# PIC32MZ.net
KiCad netlist of a schematic drawn in Altium Designer
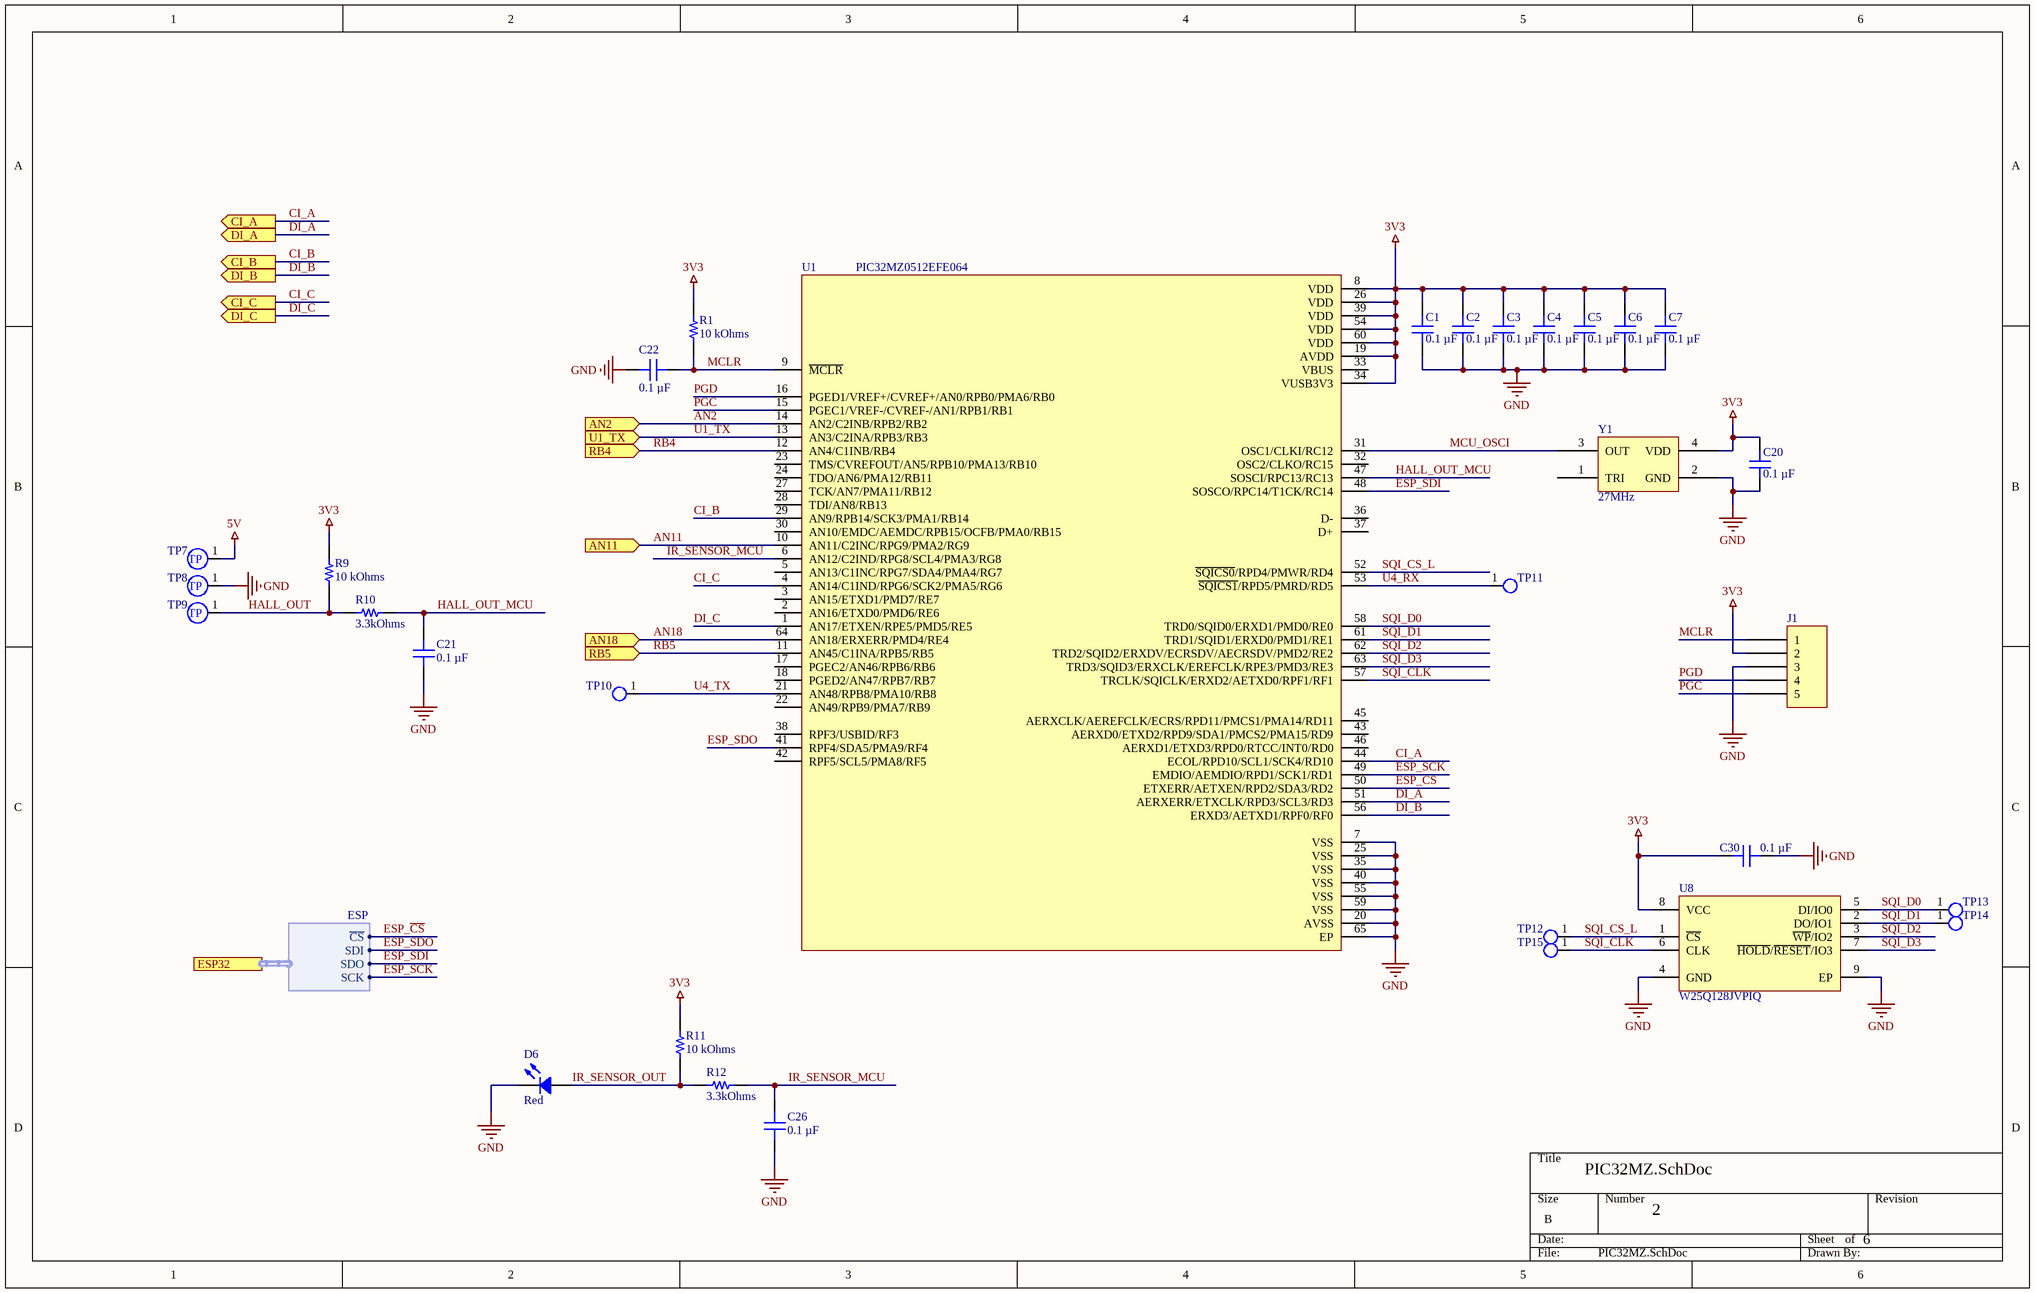
[diagram p0: PIC32MZ.SchDoc]

(export (version "E")
  (design (tool "Eeschema 10.0.6"))
  (components
    (comp (ref "C1")
      (value "0.1 µF")
      (footprint "CAP 0402_1005")
      (description "CAP CER 0.1UF 25V X5R 0402")
      (fields
        (field (name "PART NUMBER") "C1005X5R1E104K050BC")
        (field (name "MANUFACTURER") "TDK Corporation")
      )
      (libsource (lib "Celestial Altium Library - altium_library") (part "Capacitor"))
    )
    (comp (ref "C2")
      (value "0.1 µF")
      (footprint "CAP 0402_1005")
      (description "CAP CER 0.1UF 25V X5R 0402")
      (fields
        (field (name "PART NUMBER") "C1005X5R1E104K050BC")
        (field (name "MANUFACTURER") "TDK Corporation")
      )
      (libsource (lib "Celestial Altium Library - altium_library") (part "Capacitor"))
    )
    (comp (ref "C3")
      (value "0.1 µF")
      (footprint "CAP 0402_1005")
      (description "CAP CER 0.1UF 25V X5R 0402")
      (fields
        (field (name "PART NUMBER") "C1005X5R1E104K050BC")
        (field (name "MANUFACTURER") "TDK Corporation")
      )
      (libsource (lib "Celestial Altium Library - altium_library") (part "Capacitor"))
    )
    (comp (ref "C4")
      (value "0.1 µF")
      (footprint "CAP 0402_1005")
      (description "CAP CER 0.1UF 25V X5R 0402")
      (fields
        (field (name "PART NUMBER") "C1005X5R1E104K050BC")
        (field (name "MANUFACTURER") "TDK Corporation")
      )
      (libsource (lib "Celestial Altium Library - altium_library") (part "Capacitor"))
    )
    (comp (ref "C5")
      (value "0.1 µF")
      (footprint "CAP 0402_1005")
      (description "CAP CER 0.1UF 25V X5R 0402")
      (fields
        (field (name "PART NUMBER") "C1005X5R1E104K050BC")
        (field (name "MANUFACTURER") "TDK Corporation")
      )
      (libsource (lib "Celestial Altium Library - altium_library") (part "Capacitor"))
    )
    (comp (ref "C6")
      (value "0.1 µF")
      (footprint "CAP 0402_1005")
      (description "CAP CER 0.1UF 25V X5R 0402")
      (fields
        (field (name "PART NUMBER") "C1005X5R1E104K050BC")
        (field (name "MANUFACTURER") "TDK Corporation")
      )
      (libsource (lib "Celestial Altium Library - altium_library") (part "Capacitor"))
    )
    (comp (ref "C7")
      (value "0.1 µF")
      (footprint "CAP 0402_1005")
      (description "CAP CER 0.1UF 25V X5R 0402")
      (fields
        (field (name "PART NUMBER") "C1005X5R1E104K050BC")
        (field (name "MANUFACTURER") "TDK Corporation")
      )
      (libsource (lib "Celestial Altium Library - altium_library") (part "Capacitor"))
    )
    (comp (ref "C20")
      (value "0.1 µF")
      (footprint "CAP 0402_1005")
      (description "CAP CER 0.1UF 16V X7R 0402")
      (fields (field (name "PART NUMBER") "C0402C104K4RACAUTO") (field (name "MANUFACTURER") "KEMET"))
      (libsource (lib "Celestial Altium Library - altium_library") (part "Capacitor"))
    )
    (comp (ref "C21")
      (value "0.1 µF")
      (footprint "CAP 0402_1005")
      (description "CAP CER 0.1UF 25V X5R 0402")
      (fields
        (field (name "PART NUMBER") "C1005X5R1E104K050BC")
        (field (name "MANUFACTURER") "TDK Corporation")
      )
      (libsource (lib "Celestial Altium Library - altium_library") (part "Capacitor"))
    )
    (comp (ref "C22")
      (value "0.1 µF")
      (footprint "CAP 0402_1005")
      (description "CAP CER 0.1UF 25V X5R 0402")
      (fields
        (field (name "PART NUMBER") "C1005X5R1E104K050BC")
        (field (name "MANUFACTURER") "TDK Corporation")
      )
      (libsource (lib "Celestial Altium Library - altium_library") (part "Capacitor"))
    )
    (comp (ref "C26")
      (value "0.1 µF")
      (footprint "CAP 0402_1005")
      (description "CAP CER 0.1UF 25V X5R 0402")
      (fields
        (field (name "PART NUMBER") "C1005X5R1E104K050BC")
        (field (name "MANUFACTURER") "TDK Corporation")
      )
      (libsource (lib "Celestial Altium Library - altium_library") (part "Capacitor"))
    )
    (comp (ref "C30")
      (value "0.1 µF")
      (footprint "CAP 0402_1005")
      (description "CAP CER 0.1UF 25V X5R 0402")
      (fields
        (field (name "PART NUMBER") "C1005X5R1E104K050BC")
        (field (name "MANUFACTURER") "TDK Corporation")
      )
      (libsource (lib "Celestial Altium Library - altium_library") (part "Capacitor"))
    )
    (comp (ref "D6")
      (value "Red")
      (footprint "LED 0603_1608 RED")
      (description "LED RED CLEAR 0603 SMD")
      (fields (field (name "PART NUMBER") "5988010107F") (field (name "MANUFACTURER") "Dialight"))
      (libsource (lib "Celestial Altium Library - altium_library") (part "LED"))
    )
    (comp (ref "J1")
      (value "SM05B-SRSS-TB(LF)(SN)")
      (footprint "JST SM05B-SRSS-TB")
      (description "CONN HEADER SMD R/A 5POS 1MM")
      (fields (field (name "MANUFACTURER") "JST Sales America Inc."))
      (libsource (lib "Celestial Altium Library - altium_library") (part "5 Pin"))
    )
    (comp (ref "R1")
      (value "10 kOhms")
      (footprint "RES 0402_1005")
      (description "RES SMD 10K OHM 0.5% 1/16W 0402")
      (fields (field (name "PART NUMBER") "CRCW040210K0DHEDP") (field (name "MANUFACTURER") "Vishay Dale"))
      (libsource (lib "Celestial Altium Library - altium_library") (part "Resistor"))
    )
    (comp (ref "R9")
      (value "10 kOhms")
      (footprint "RES 0402_1005")
      (description "RES SMD 10K OHM 0.5% 1/16W 0402")
      (fields (field (name "PART NUMBER") "CRCW040210K0DHEDP") (field (name "MANUFACTURER") "Vishay Dale"))
      (libsource (lib "Celestial Altium Library - altium_library") (part "Resistor"))
    )
    (comp (ref "R10")
      (value "3.3kOhms")
      (footprint "RES 0402_1005")
      (description "RES SMD 10K OHM 0.5% 1/16W 0402")
      (fields (field (name "PART NUMBER") "CRCW040210K0DHEDP") (field (name "MANUFACTURER") "Vishay Dale"))
      (libsource (lib "Celestial Altium Library - altium_library") (part "Resistor"))
    )
    (comp (ref "R11")
      (value "10 kOhms")
      (footprint "RES 0402_1005")
      (description "RES SMD 10K OHM 0.5% 1/16W 0402")
      (fields (field (name "PART NUMBER") "CRCW040210K0DHEDP") (field (name "MANUFACTURER") "Vishay Dale"))
      (libsource (lib "Celestial Altium Library - altium_library") (part "Resistor"))
    )
    (comp (ref "R12")
      (value "3.3kOhms")
      (footprint "RES 0402_1005")
      (description "RES SMD 10K OHM 0.5% 1/16W 0402")
      (fields (field (name "PART NUMBER") "CRCW040210K0DHEDP") (field (name "MANUFACTURER") "Vishay Dale"))
      (libsource (lib "Celestial Altium Library - altium_library") (part "Resistor"))
    )
    (comp (ref "TP7")
      (value "TP")
      (footprint "TP")
      (description "Test point")
      (libsource (lib "IC") (part "TP"))
    )
    (comp (ref "TP8")
      (value "TP")
      (footprint "TP")
      (description "Test point")
      (libsource (lib "IC") (part "TP"))
    )
    (comp (ref "TP9")
      (value "TP")
      (footprint "TP")
      (description "Test point")
      (libsource (lib "IC") (part "TP"))
    )
    (comp (ref "TP10")
      (value "0.8mm")
      (footprint "TP  0.8mm")
      (description "Test point")
      (libsource (lib "IC") (part "TP 0.8mm"))
    )
    (comp (ref "TP11")
      (value "0.8mm")
      (footprint "TP  0.8mm")
      (description "Test point")
      (libsource (lib "IC") (part "TP 0.8mm"))
    )
    (comp (ref "TP12")
      (value "0.8mm")
      (footprint "TP  0.8mm")
      (description "Test point")
      (libsource (lib "IC") (part "TP 0.8mm"))
    )
    (comp (ref "TP13")
      (value "0.8mm")
      (footprint "TP  0.8mm")
      (description "Test point")
      (libsource (lib "IC") (part "TP 0.8mm"))
    )
    (comp (ref "TP14")
      (value "0.8mm")
      (footprint "TP  0.8mm")
      (description "Test point")
      (libsource (lib "IC") (part "TP 0.8mm"))
    )
    (comp (ref "TP15")
      (value "0.8mm")
      (footprint "TP  0.8mm")
      (description "Test point")
      (libsource (lib "IC") (part "TP 0.8mm"))
    )
    (comp (ref "U1")
      (value "PIC32MZ0512EFE064")
      (footprint "QFN50P900X900X100-65N")
      (description "32-bit Microcontrollers - MCU 32-BIT MCU 512KB FL 128KB RAM, No Crypto")
      (fields (field (name "MF") "Microchip") (field (name "MP") "PIC32MZ2048EFG064T-I/PT"))
      (libsource (lib "IC") (part "PIC32MZ0512EFE064-I/PT"))
    )
    (comp (ref "U8")
      (value "W25Q128JVPIQ")
      (footprint "WSON-8 6x5 Winbond")
      (description "Quad SPI FLASH 16MB")
      (libsource (lib "IC") (part "W25Q128JVPIQ"))
    )
    (comp (ref "Y1")
      (value "27MHz")
      (footprint "ABRACON ASD")
      (description "XTAL OSC XO 27.0000MHZ HCMOS SMD")
      (fields (field (name "PART NUMBER") "ASD3-27.000MHZ-EC-T") (field (name "MANUFACTURER") "Abracon LLC"))
      (libsource (lib "Celestial Altium Library - altium_library") (part "Abracon XO ASD"))
    )
  )
  (nets
    (net (code "2") (name "/AN2") (class "Default")
      (node (ref "U1") (pin "14") (pinfunction "AN2/C2INB/RPB2/RB2_14") (pintype "passive"))
    )
    (net (code "3") (name "/AN11") (class "Default")
      (node (ref "U1") (pin "10") (pinfunction "AN11/C2INC/RPG9/PMA2/RG9_10") (pintype "passive"))
    )
    (net (code "4") (name "/AN18") (class "Default")
      (node (ref "U1") (pin "64") (pinfunction "AN18/ERXERR/PMD4/RE4_64") (pintype "passive"))
    )
    (net (code "5") (name "/CI_A") (class "Default")
      (node (ref "U1") (pin "44") (pinfunction "ECOL/RPD10/SCL1/SCK4/RD10_44") (pintype "passive"))
    )
    (net (code "6") (name "/CI_B") (class "Default")
      (node (ref "U1") (pin "29") (pinfunction "AN9/RPB14/SCK3/PMA1/RB14_29") (pintype "passive"))
    )
    (net (code "7") (name "/CI_C") (class "Default")
      (node (ref "U1") (pin "4") (pinfunction "AN14/C1IND/RPG6/SCK2/PMA5/RG6_4") (pintype "passive"))
    )
    (net (code "8") (name "/DI_A") (class "Default")
      (node (ref "U1") (pin "51") (pinfunction "AERXERR/ETXCLK/RPD3/SCL3/RD3_51") (pintype "passive"))
    )
    (net (code "9") (name "/DI_B") (class "Default")
      (node (ref "U1") (pin "56") (pinfunction "ERXD3/AETXD1/RPF0/RF0_56") (pintype "passive"))
    )
    (net (code "10") (name "/DI_C") (class "Default")
      (node (ref "U1") (pin "1") (pinfunction "AN17/ETXEN/RPE5/PMD5/RE5_1") (pintype "passive"))
    )
    (net (code "11") (name "/ESP_SCK") (class "Default")
      (node (ref "U1") (pin "49") (pinfunction "EMDIO/AEMDIO/RPD1/SCK1/RD1_49") (pintype "passive"))
    )
    (net (code "12") (name "/ESP_SDI") (class "Default")
      (node (ref "U1") (pin "48") (pinfunction "SOSCO/RPC14/T1CK/RC14_48") (pintype "passive"))
    )
    (net (code "13") (name "/ESP_SDO") (class "Default")
      (node (ref "U1") (pin "41") (pinfunction "RPF4/SDA5/PMA9/RF4_41") (pintype "passive"))
    )
    (net (code "14") (name "/ESP_~{CS}") (class "Default")
      (node (ref "U1") (pin "50") (pinfunction "ETXERR/AETXEN/RPD2/SDA3/RD2_50") (pintype "passive"))
    )
    (net (code "15") (name "/HALL_OUT") (class "Default")
      (node (ref "R10") (pin "2") (pinfunction "2_2") (pintype "passive"))
      (node (ref "R9") (pin "1") (pinfunction "1_1") (pintype "passive"))
      (node (ref "TP9") (pin "1") (pinfunction "TP_1") (pintype "passive"))
    )
    (net (code "16") (name "/HALL_OUT_MCU") (class "Default")
      (node (ref "C21") (pin "1") (pinfunction "1_1") (pintype "passive"))
      (node (ref "R10") (pin "1") (pinfunction "1_1") (pintype "passive"))
      (node (ref "U1") (pin "47") (pinfunction "SOSCI/RPC13/RC13_47") (pintype "passive"))
    )
    (net (code "17") (name "/IR_SENSOR_MCU") (class "Default")
      (node (ref "C26") (pin "1") (pinfunction "1_1") (pintype "passive"))
      (node (ref "R12") (pin "1") (pinfunction "1_1") (pintype "passive"))
      (node (ref "U1") (pin "6") (pinfunction "AN12/C2IND/RPG8/SCL4/PMA3/RG8_6") (pintype "passive"))
    )
    (net (code "18") (name "/IR_SENSOR_OUT") (class "Default")
      (node (ref "D6") (pin "1") (pinfunction "1_1") (pintype "passive"))
      (node (ref "R11") (pin "1") (pinfunction "1_1") (pintype "passive"))
      (node (ref "R12") (pin "2") (pinfunction "2_2") (pintype "passive"))
    )
    (net (code "19") (name "/MCLR") (class "Default")
      (node (ref "C22") (pin "2") (pinfunction "2_2") (pintype "passive"))
      (node (ref "J1") (pin "1") (pinfunction "1_1") (pintype "passive"))
      (node (ref "R1") (pin "1") (pinfunction "1_1") (pintype "passive"))
      (node (ref "U1") (pin "9") (pinfunction "~{MCLR}_9") (pintype "passive"))
    )
    (net (code "20") (name "/MCU_OSCI") (class "Default")
      (node (ref "U1") (pin "31") (pinfunction "OSC1/CLKI/RC12_31") (pintype "passive"))
      (node (ref "Y1") (pin "3") (pinfunction "OUT_3") (pintype "passive"))
    )
    (net (code "21") (name "/PGC") (class "Default")
      (node (ref "J1") (pin "5") (pinfunction "5_5") (pintype "passive"))
      (node (ref "U1") (pin "15") (pinfunction "PGEC1/VREF-/CVREF-/AN1/RPB1/RB1_15") (pintype "passive"))
    )
    (net (code "22") (name "/PGD") (class "Default")
      (node (ref "J1") (pin "4") (pinfunction "4_4") (pintype "passive"))
      (node (ref "U1") (pin "16") (pinfunction "PGED1/VREF+/CVREF+/AN0/RPB0/PMA6/RB0_16") (pintype "passive"))
    )
    (net (code "23") (name "/RB4") (class "Default")
      (node (ref "U1") (pin "12") (pinfunction "AN4/C1INB/RB4_12") (pintype "passive"))
    )
    (net (code "24") (name "/RB5") (class "Default")
      (node (ref "U1") (pin "11") (pinfunction "AN45/C1INA/RPB5/RB5_11") (pintype "passive"))
    )
    (net (code "25") (name "/SQI_CLK") (class "Default")
      (node (ref "TP15") (pin "1") (pinfunction "TP_1") (pintype "passive"))
      (node (ref "U1") (pin "57") (pinfunction "TRCLK/SQICLK/ERXD2/AETXD0/RPF1/RF1_57") (pintype "passive"))
      (node (ref "U8") (pin "6") (pinfunction "CLK_6") (pintype "passive"))
    )
    (net (code "26") (name "/SQI_CS_L") (class "Default")
      (node (ref "TP12") (pin "1") (pinfunction "TP_1") (pintype "passive"))
      (node (ref "U1") (pin "52") (pinfunction "~{SQICS0}/RPD4/PMWR/RD4_52") (pintype "passive"))
      (node (ref "U8") (pin "1") (pinfunction "~{CS}_1") (pintype "passive"))
    )
    (net (code "27") (name "/SQI_D0") (class "Default")
      (node (ref "TP13") (pin "1") (pinfunction "TP_1") (pintype "passive"))
      (node (ref "U1") (pin "58") (pinfunction "TRD0/SQID0/ERXD1/PMD0/RE0_58") (pintype "passive"))
      (node (ref "U8") (pin "5") (pinfunction "DI/IO0_5") (pintype "passive"))
    )
    (net (code "28") (name "/SQI_D1") (class "Default")
      (node (ref "TP14") (pin "1") (pinfunction "TP_1") (pintype "passive"))
      (node (ref "U1") (pin "61") (pinfunction "TRD1/SQID1/ERXD0/PMD1/RE1_61") (pintype "passive"))
      (node (ref "U8") (pin "2") (pinfunction "DO/IO1_2") (pintype "passive"))
    )
    (net (code "29") (name "/SQI_D2") (class "Default")
      (node (ref "U1") (pin "62") (pinfunction "TRD2/SQID2/ERXDV/ECRSDV/AECRSDV/PMD2/RE2_62") (pintype "passive"))
      (node (ref "U8") (pin "3") (pinfunction "~{WP}/IO2_3") (pintype "passive"))
    )
    (net (code "30") (name "/SQI_D3") (class "Default")
      (node (ref "U1") (pin "63") (pinfunction "TRD3/SQID3/ERXCLK/EREFCLK/RPE3/PMD3/RE3_63") (pintype "passive"))
      (node (ref "U8") (pin "7") (pinfunction "~{HOLD}/~{RESET}/IO3_7") (pintype "passive"))
    )
    (net (code "31") (name "/U1_TX") (class "Default")
      (node (ref "U1") (pin "13") (pinfunction "AN3/C2INA/RPB3/RB3_13") (pintype "passive"))
    )
    (net (code "32") (name "/U4_RX") (class "Default")
      (node (ref "TP11") (pin "1") (pinfunction "TP_1") (pintype "passive"))
      (node (ref "U1") (pin "53") (pinfunction "~{SQICS1}/RPD5/PMRD/RD5_53") (pintype "passive"))
    )
    (net (code "33") (name "/U4_TX") (class "Default")
      (node (ref "TP10") (pin "1") (pinfunction "TP_1") (pintype "passive"))
      (node (ref "U1") (pin "21") (pinfunction "AN48/RPB8/PMA10/RB8_21") (pintype "passive"))
    )
    (net (code "35") (name "3V3") (class "Default")
      (node (ref "C1") (pin "2") (pinfunction "2_2") (pintype "passive"))
      (node (ref "C2") (pin "2") (pinfunction "2_2") (pintype "passive"))
      (node (ref "C20") (pin "2") (pinfunction "2_2") (pintype "passive"))
      (node (ref "C3") (pin "2") (pinfunction "2_2") (pintype "passive"))
      (node (ref "C30") (pin "2") (pinfunction "2_2") (pintype "passive"))
      (node (ref "C4") (pin "2") (pinfunction "2_2") (pintype "passive"))
      (node (ref "C5") (pin "2") (pinfunction "2_2") (pintype "passive"))
      (node (ref "C6") (pin "2") (pinfunction "2_2") (pintype "passive"))
      (node (ref "C7") (pin "2") (pinfunction "2_2") (pintype "passive"))
      (node (ref "J1") (pin "2") (pinfunction "2_2") (pintype "passive"))
      (node (ref "R1") (pin "2") (pinfunction "2_2") (pintype "passive"))
      (node (ref "R11") (pin "2") (pinfunction "2_2") (pintype "passive"))
      (node (ref "R9") (pin "2") (pinfunction "2_2") (pintype "passive"))
      (node (ref "U1") (pin "19") (pinfunction "AVDD_19") (pintype "power_in"))
      (node (ref "U1") (pin "26") (pinfunction "VDD_26") (pintype "power_in"))
      (node (ref "U1") (pin "34") (pinfunction "VUSB3V3_34") (pintype "power_in"))
      (node (ref "U1") (pin "39") (pinfunction "VDD_39") (pintype "power_in"))
      (node (ref "U1") (pin "54") (pinfunction "VDD_54") (pintype "power_in"))
      (node (ref "U1") (pin "60") (pinfunction "VDD_60") (pintype "power_in"))
      (node (ref "U1") (pin "8") (pinfunction "VDD_8") (pintype "power_in"))
      (node (ref "U8") (pin "8") (pinfunction "VCC_8") (pintype "passive"))
      (node (ref "Y1") (pin "4") (pinfunction "VDD_4") (pintype "passive"))
    )
    (net (code "36") (name "5V") (class "Default")
      (node (ref "TP7") (pin "1") (pinfunction "TP_1") (pintype "passive"))
    )
    (net (code "37") (name "GND") (class "Default")
      (node (ref "C1") (pin "1") (pinfunction "1_1") (pintype "passive"))
      (node (ref "C2") (pin "1") (pinfunction "1_1") (pintype "passive"))
      (node (ref "C20") (pin "1") (pinfunction "1_1") (pintype "passive"))
      (node (ref "C21") (pin "2") (pinfunction "2_2") (pintype "passive"))
      (node (ref "C22") (pin "1") (pinfunction "1_1") (pintype "passive"))
      (node (ref "C26") (pin "2") (pinfunction "2_2") (pintype "passive"))
      (node (ref "C3") (pin "1") (pinfunction "1_1") (pintype "passive"))
      (node (ref "C30") (pin "1") (pinfunction "1_1") (pintype "passive"))
      (node (ref "C4") (pin "1") (pinfunction "1_1") (pintype "passive"))
      (node (ref "C5") (pin "1") (pinfunction "1_1") (pintype "passive"))
      (node (ref "C6") (pin "1") (pinfunction "1_1") (pintype "passive"))
      (node (ref "C7") (pin "1") (pinfunction "1_1") (pintype "passive"))
      (node (ref "D6") (pin "2") (pinfunction "2_2") (pintype "passive"))
      (node (ref "J1") (pin "3") (pinfunction "3_3") (pintype "passive"))
      (node (ref "TP8") (pin "1") (pinfunction "TP_1") (pintype "passive"))
      (node (ref "U1") (pin "20") (pinfunction "AVSS_20") (pintype "power_in"))
      (node (ref "U1") (pin "25") (pinfunction "VSS_25") (pintype "power_in"))
      (node (ref "U1") (pin "35") (pinfunction "VSS_35") (pintype "power_in"))
      (node (ref "U1") (pin "40") (pinfunction "VSS_40") (pintype "power_in"))
      (node (ref "U1") (pin "55") (pinfunction "VSS_55") (pintype "power_in"))
      (node (ref "U1") (pin "59") (pinfunction "VSS_59") (pintype "power_in"))
      (node (ref "U1") (pin "65") (pinfunction "EP_65") (pintype "power_in"))
      (node (ref "U1") (pin "7") (pinfunction "VSS_7") (pintype "power_in"))
      (node (ref "U8") (pin "4") (pinfunction "GND_4") (pintype "passive"))
      (node (ref "U8") (pin "9") (pinfunction "EP_9") (pintype "passive"))
      (node (ref "Y1") (pin "2") (pinfunction "GND_2") (pintype "passive"))
    )
    (net (code "38") (name "unconnected-(U1-AERXCLK{slash}AEREFCLK{slash}ECRS{slash}RPD11{slash}PMCS1{slash}PMA14{slash}RD11-Pad45)") (class "Default")
      (node (ref "U1") (pin "45") (pinfunction "AERXCLK/AEREFCLK/ECRS/RPD11/PMCS1/PMA14/RD11_45") (pintype "passive"))
    )
    (net (code "39") (name "unconnected-(U1-AERXD0{slash}ETXD2{slash}RPD9{slash}SDA1{slash}PMCS2{slash}PMA15{slash}RD9-Pad43)") (class "Default")
      (node (ref "U1") (pin "43") (pinfunction "AERXD0/ETXD2/RPD9/SDA1/PMCS2/PMA15/RD9_43") (pintype "passive"))
    )
    (net (code "40") (name "unconnected-(U1-AERXD1{slash}ETXD3{slash}RPD0{slash}RTCC{slash}INT0{slash}RD0-Pad46)") (class "Default")
      (node (ref "U1") (pin "46") (pinfunction "AERXD1/ETXD3/RPD0/RTCC/INT0/RD0_46") (pintype "passive"))
    )
    (net (code "41") (name "unconnected-(U1-AN10{slash}EMDC{slash}AEMDC{slash}RPB15{slash}OCFB{slash}PMA0{slash}RB15-Pad30)") (class "Default")
      (node (ref "U1") (pin "30") (pinfunction "AN10/EMDC/AEMDC/RPB15/OCFB/PMA0/RB15_30") (pintype "passive"))
    )
    (net (code "42") (name "unconnected-(U1-AN13{slash}C1INC{slash}RPG7{slash}SDA4{slash}PMA4{slash}RG7-Pad5)") (class "Default")
      (node (ref "U1") (pin "5") (pinfunction "AN13/C1INC/RPG7/SDA4/PMA4/RG7_5") (pintype "passive"))
    )
    (net (code "43") (name "unconnected-(U1-AN15{slash}ETXD1{slash}PMD7{slash}RE7-Pad3)") (class "Default")
      (node (ref "U1") (pin "3") (pinfunction "AN15/ETXD1/PMD7/RE7_3") (pintype "passive"))
    )
    (net (code "44") (name "unconnected-(U1-AN16{slash}ETXD0{slash}PMD6{slash}RE6-Pad2)") (class "Default")
      (node (ref "U1") (pin "2") (pinfunction "AN16/ETXD0/PMD6/RE6_2") (pintype "passive"))
    )
    (net (code "45") (name "unconnected-(U1-AN49{slash}RPB9{slash}PMA7{slash}RB9-Pad22)") (class "Default")
      (node (ref "U1") (pin "22") (pinfunction "AN49/RPB9/PMA7/RB9_22") (pintype "passive"))
    )
    (net (code "46") (name "unconnected-(U1-D+-Pad37)") (class "Default")
      (node (ref "U1") (pin "37") (pinfunction "D+_37") (pintype "passive"))
    )
    (net (code "47") (name "unconnected-(U1-D--Pad36)") (class "Default")
      (node (ref "U1") (pin "36") (pinfunction "D-_36") (pintype "passive"))
    )
    (net (code "48") (name "unconnected-(U1-OSC2{slash}CLKO{slash}RC15-Pad32)") (class "Default")
      (node (ref "U1") (pin "32") (pinfunction "OSC2/CLKO/RC15_32") (pintype "passive"))
    )
    (net (code "49") (name "unconnected-(U1-PGEC2{slash}AN46{slash}RPB6{slash}RB6-Pad17)") (class "Default")
      (node (ref "U1") (pin "17") (pinfunction "PGEC2/AN46/RPB6/RB6_17") (pintype "passive"))
    )
    (net (code "50") (name "unconnected-(U1-PGED2{slash}AN47{slash}RPB7{slash}RB7-Pad18)") (class "Default")
      (node (ref "U1") (pin "18") (pinfunction "PGED2/AN47/RPB7/RB7_18") (pintype "passive"))
    )
    (net (code "51") (name "unconnected-(U1-RPF3{slash}USBID{slash}RF3-Pad38)") (class "Default")
      (node (ref "U1") (pin "38") (pinfunction "RPF3/USBID/RF3_38") (pintype "passive"))
    )
    (net (code "52") (name "unconnected-(U1-RPF5{slash}SCL5{slash}PMA8{slash}RF5-Pad42)") (class "Default")
      (node (ref "U1") (pin "42") (pinfunction "RPF5/SCL5/PMA8/RF5_42") (pintype "passive"))
    )
    (net (code "53") (name "unconnected-(U1-TCK{slash}AN7{slash}PMA11{slash}RB12-Pad27)") (class "Default")
      (node (ref "U1") (pin "27") (pinfunction "TCK/AN7/PMA11/RB12_27") (pintype "passive"))
    )
    (net (code "54") (name "unconnected-(U1-TDI{slash}AN8{slash}RB13-Pad28)") (class "Default")
      (node (ref "U1") (pin "28") (pinfunction "TDI/AN8/RB13_28") (pintype "passive"))
    )
    (net (code "55") (name "unconnected-(U1-TDO{slash}AN6{slash}PMA12{slash}RB11-Pad24)") (class "Default")
      (node (ref "U1") (pin "24") (pinfunction "TDO/AN6/PMA12/RB11_24") (pintype "passive"))
    )
    (net (code "56") (name "unconnected-(U1-TMS{slash}CVREFOUT{slash}AN5{slash}RPB10{slash}PMA13{slash}RB10-Pad23)") (class "Default")
      (node (ref "U1") (pin "23") (pinfunction "TMS/CVREFOUT/AN5/RPB10/PMA13/RB10_23") (pintype "passive"))
    )
    (net (code "57") (name "unconnected-(U1-VBUS-Pad33)") (class "Default")
      (node (ref "U1") (pin "33") (pinfunction "VBUS_33") (pintype "power_in"))
    )
    (net (code "58") (name "unconnected-(Y1-TRI-Pad1)") (class "Default")
      (node (ref "Y1") (pin "1") (pinfunction "TRI_1") (pintype "passive"))
    )
  )
)
